# 08-AUDIO_AUX.net
KiCad netlist of a schematic drawn in Altium Designer
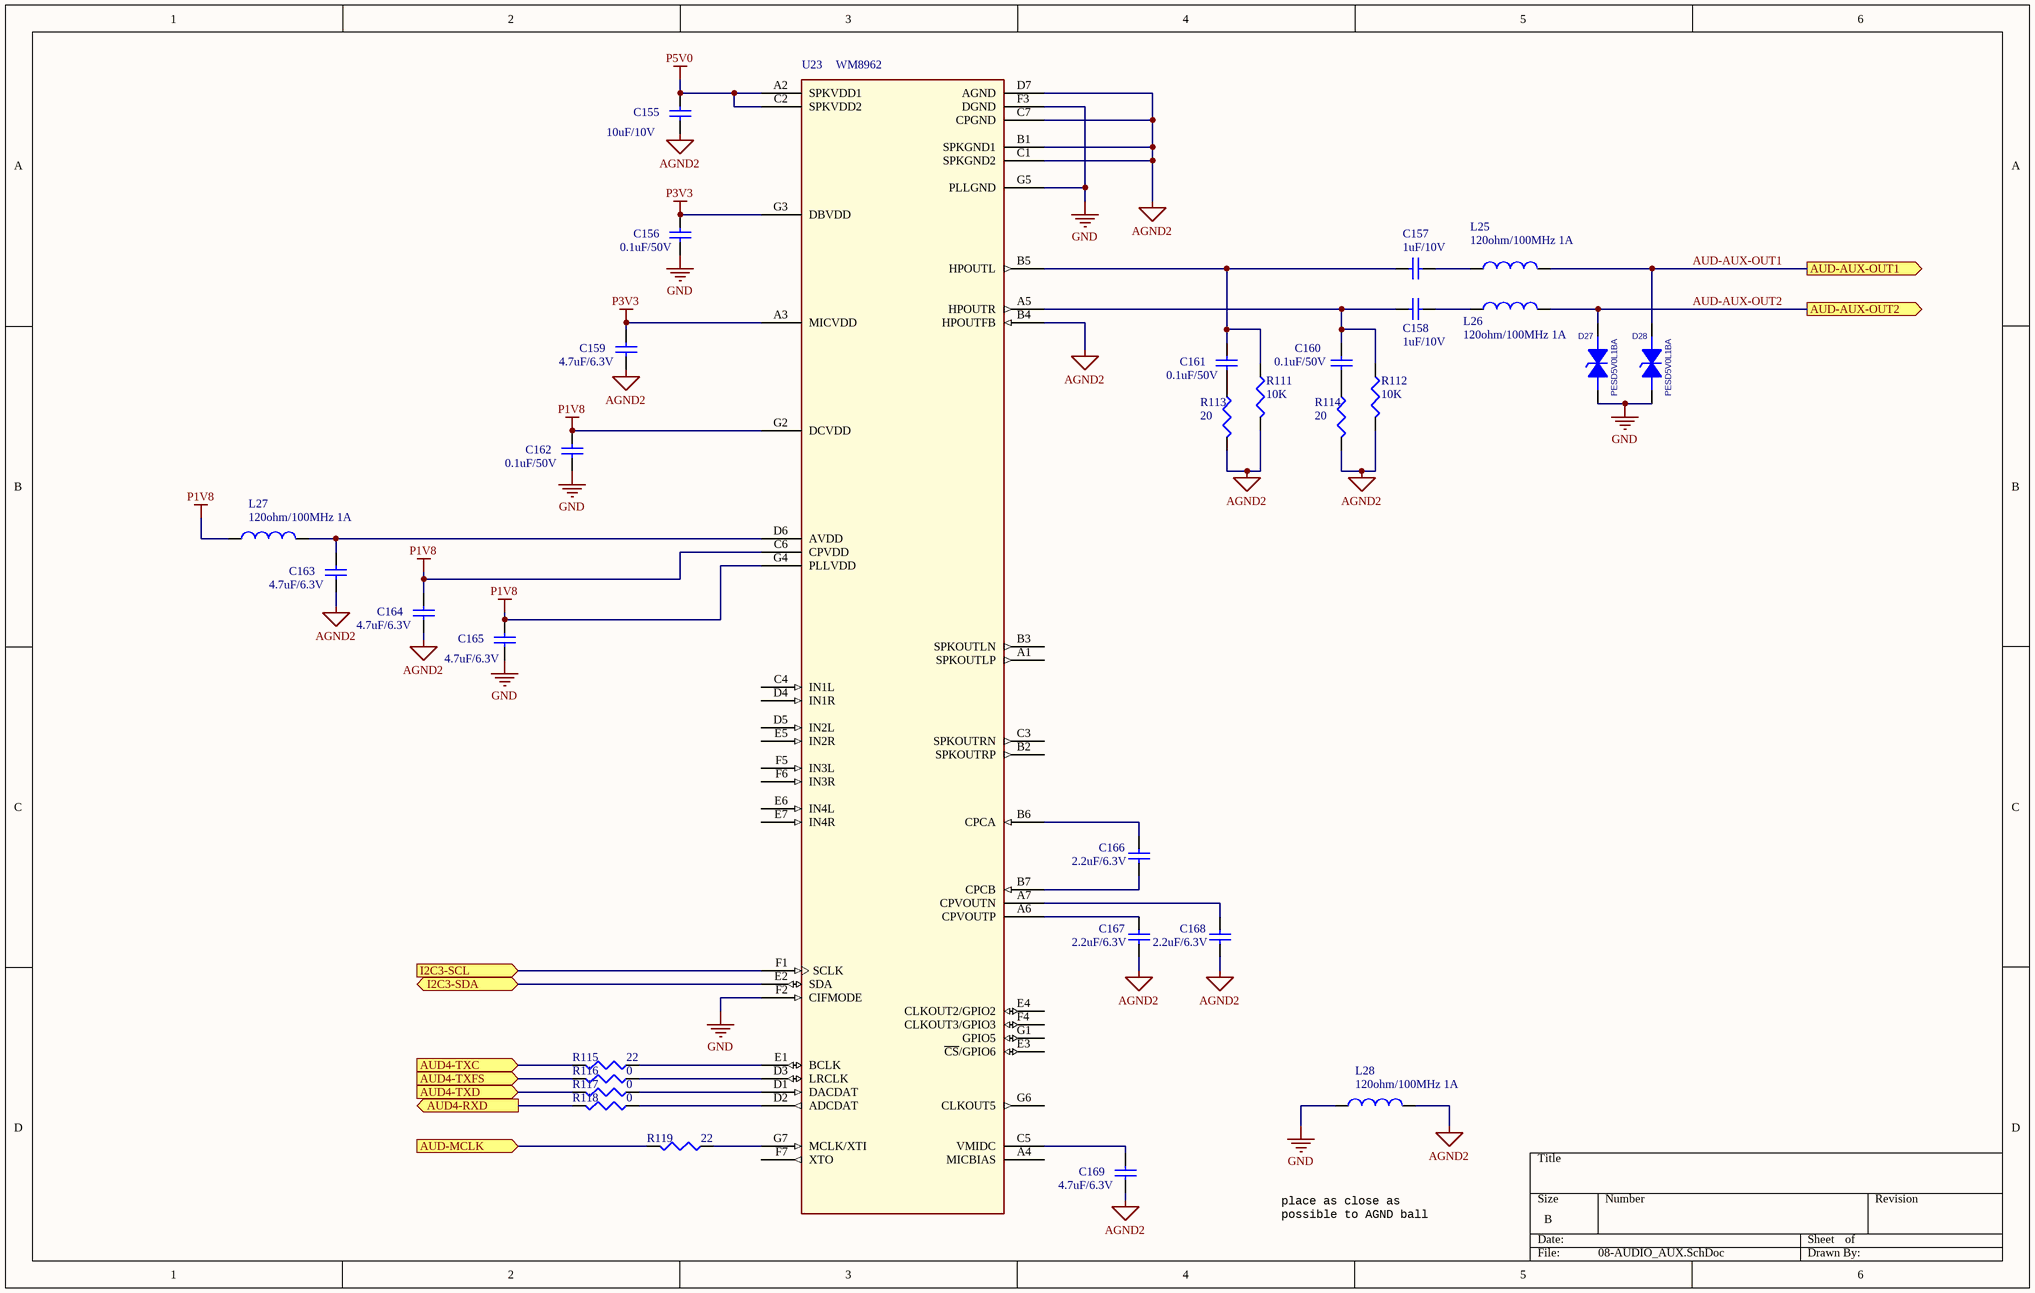
[diagram p0: 08-AUDIO_AUX.SchDoc]

(export (version "E")
  (design (tool "Eeschema 10.0.6"))
  (components
    (comp (ref "C155")
      (value "10uF/10V")
      (footprint "0805")
      (description "Capacitor")
      (fields (field (name "PUBLISHER") "Altium Limited"))
      (libsource (lib "Miscellaneous Devices") (part "Cap"))
    )
    (comp (ref "C156")
      (value "0.1uF/50V")
      (footprint "0402")
      (description "Capacitor")
      (fields (field (name "PUBLISHER") "Altium Limited"))
      (libsource (lib "Miscellaneous Devices") (part "Cap"))
    )
    (comp (ref "C157")
      (value "1uF/10V")
      (footprint "0402")
      (description "Capacitor")
      (fields (field (name "PUBLISHER") "Altium Limited"))
      (libsource (lib "Miscellaneous Devices") (part "Cap"))
    )
    (comp (ref "C158")
      (value "1uF/10V")
      (footprint "0402")
      (description "Capacitor")
      (fields (field (name "PUBLISHER") "Altium Limited"))
      (libsource (lib "Miscellaneous Devices") (part "Cap"))
    )
    (comp (ref "C159")
      (value "4.7uF/6.3V")
      (footprint "0603")
      (description "Capacitor")
      (fields (field (name "PUBLISHER") "Altium Limited"))
      (libsource (lib "Miscellaneous Devices") (part "Cap"))
    )
    (comp (ref "C160")
      (value "0.1uF/50V")
      (footprint "0402")
      (description "Capacitor")
      (fields (field (name "PUBLISHER") "Altium Limited"))
      (libsource (lib "Miscellaneous Devices") (part "Cap"))
    )
    (comp (ref "C161")
      (value "0.1uF/50V")
      (footprint "0402")
      (description "Capacitor")
      (fields (field (name "PUBLISHER") "Altium Limited"))
      (libsource (lib "Miscellaneous Devices") (part "Cap"))
    )
    (comp (ref "C162")
      (value "0.1uF/50V")
      (footprint "0402")
      (description "Capacitor")
      (fields (field (name "PUBLISHER") "Altium Limited"))
      (libsource (lib "Miscellaneous Devices") (part "Cap"))
    )
    (comp (ref "C163")
      (value "4.7uF/6.3V")
      (footprint "0603")
      (description "Capacitor")
      (fields (field (name "PUBLISHER") "Altium Limited"))
      (libsource (lib "Miscellaneous Devices") (part "Cap"))
    )
    (comp (ref "C164")
      (value "4.7uF/6.3V")
      (footprint "0603")
      (description "Capacitor")
      (fields (field (name "PUBLISHER") "Altium Limited"))
      (libsource (lib "Miscellaneous Devices") (part "Cap"))
    )
    (comp (ref "C165")
      (value "4.7uF/6.3V")
      (footprint "0603")
      (description "Capacitor")
      (fields (field (name "PUBLISHER") "Altium Limited"))
      (libsource (lib "Miscellaneous Devices") (part "Cap"))
    )
    (comp (ref "C166")
      (value "2.2uF/6.3V")
      (footprint "0402")
      (description "Capacitor")
      (fields (field (name "PUBLISHER") "Altium Limited"))
      (libsource (lib "Miscellaneous Devices") (part "Cap"))
    )
    (comp (ref "C167")
      (value "2.2uF/6.3V")
      (footprint "0402")
      (description "Capacitor")
      (fields (field (name "PUBLISHER") "Altium Limited"))
      (libsource (lib "Miscellaneous Devices") (part "Cap"))
    )
    (comp (ref "C168")
      (value "2.2uF/6.3V")
      (footprint "0402")
      (description "Capacitor")
      (fields (field (name "PUBLISHER") "Altium Limited"))
      (libsource (lib "Miscellaneous Devices") (part "Cap"))
    )
    (comp (ref "C169")
      (value "4.7uF/6.3V")
      (footprint "0603")
      (description "Capacitor")
      (fields (field (name "PUBLISHER") "Altium Limited"))
      (libsource (lib "Miscellaneous Devices") (part "Cap"))
    )
    (comp (ref "D27") (value "PESD5V0L1BA") (libsource (lib "*") (part "PESD")))
    (comp (ref "D28") (value "PESD5V0L1BA") (libsource (lib "*") (part "PESD")))
    (comp (ref "L25")
      (value "120ohm/100MHz 1A")
      (footprint "0603")
      (description "Inductor")
      (fields (field (name "PUBLISHER") "Altium Limited"))
      (libsource (lib "Miscellaneous Devices") (part "Inductor"))
    )
    (comp (ref "L26")
      (value "120ohm/100MHz 1A")
      (footprint "0603")
      (description "Inductor")
      (fields (field (name "PUBLISHER") "Altium Limited"))
      (libsource (lib "Miscellaneous Devices") (part "Inductor"))
    )
    (comp (ref "L27")
      (value "120ohm/100MHz 1A")
      (footprint "0603")
      (description "Inductor")
      (fields (field (name "PUBLISHER") "Altium Limited"))
      (libsource (lib "Miscellaneous Devices") (part "Inductor"))
    )
    (comp (ref "L28")
      (value "120ohm/100MHz 1A")
      (footprint "0603")
      (description "Inductor")
      (fields (field (name "PUBLISHER") "Altium Limited"))
      (libsource (lib "Miscellaneous Devices") (part "Inductor"))
    )
    (comp (ref "R111") (value "10K") (footprint "0402") (libsource (lib "*") (part "CR16-1003FM")))
    (comp (ref "R112") (value "10K") (footprint "0402") (libsource (lib "*") (part "CR16-1003FM")))
    (comp (ref "R113") (value "20") (footprint "0402") (libsource (lib "*") (part "CR16-1003FM")))
    (comp (ref "R114") (value "20") (footprint "0402") (libsource (lib "*") (part "CR16-1003FM")))
    (comp (ref "R115") (value "22") (footprint "0402") (libsource (lib "*") (part "CR16-1003FM")))
    (comp (ref "R116") (value "0") (footprint "0402") (libsource (lib "*") (part "CR16-1003FM")))
    (comp (ref "R117") (value "0") (footprint "0402") (libsource (lib "*") (part "CR16-1003FM")))
    (comp (ref "R118") (value "0") (footprint "0402") (libsource (lib "*") (part "CR16-1003FM")))
    (comp (ref "R119") (value "22") (footprint "0402") (libsource (lib "*") (part "CR16-1003FM")))
    (comp (ref "U23")
      (value "WM8962")
      (footprint "BGA49")
      (description "IC AUDIO CODEC 24BIT DAC 2 CH ADC 1.8V BGA49")
      (libsource (lib "*") (part "WM8962_BGA_49P_CUST"))
    )
  )
  (nets
    (net (code "1") (name "/AUD-AUX-OUT1") (class "Default")
      (node (ref "D28") (pin "2") (pinfunction "2_2") (pintype "passive"))
      (node (ref "L25") (pin "2") (pinfunction "2_2") (pintype "passive"))
    )
    (net (code "2") (name "/AUD-AUX-OUT2") (class "Default")
      (node (ref "D27") (pin "2") (pinfunction "2_2") (pintype "passive"))
      (node (ref "L26") (pin "2") (pinfunction "2_2") (pintype "passive"))
    )
    (net (code "3") (name "/AUD-MCLK") (class "Default")
      (node (ref "R119") (pin "2") (pinfunction "2_2") (pintype "passive"))
    )
    (net (code "4") (name "/AUD4-RXD") (class "Default")
      (node (ref "R118") (pin "2") (pinfunction "2_2") (pintype "passive"))
    )
    (net (code "5") (name "/AUD4-TXC") (class "Default")
      (node (ref "R115") (pin "2") (pinfunction "2_2") (pintype "passive"))
    )
    (net (code "6") (name "/AUD4-TXD") (class "Default")
      (node (ref "R117") (pin "2") (pinfunction "2_2") (pintype "passive"))
    )
    (net (code "7") (name "/AUD4-TXFS") (class "Default")
      (node (ref "R116") (pin "2") (pinfunction "2_2") (pintype "passive"))
    )
    (net (code "8") (name "/I2C3-SCL") (class "Default")
      (node (ref "U23") (pin "F1") (pinfunction "SCLK_F1") (pintype "input"))
    )
    (net (code "9") (name "/I2C3-SDA") (class "Default")
      (node (ref "U23") (pin "E2") (pinfunction "SDA_E2") (pintype "bidirectional"))
    )
    (net (code "10") (name "AGND2") (class "Default")
      (node (ref "C155") (pin "1") (pinfunction "1_1") (pintype "passive"))
      (node (ref "C159") (pin "1") (pinfunction "1_1") (pintype "passive"))
      (node (ref "C163") (pin "1") (pinfunction "1_1") (pintype "passive"))
      (node (ref "C164") (pin "1") (pinfunction "1_1") (pintype "passive"))
      (node (ref "C167") (pin "1") (pinfunction "1_1") (pintype "passive"))
      (node (ref "C168") (pin "1") (pinfunction "1_1") (pintype "passive"))
      (node (ref "C169") (pin "1") (pinfunction "1_1") (pintype "passive"))
      (node (ref "L28") (pin "2") (pinfunction "2_2") (pintype "passive"))
      (node (ref "R111") (pin "2") (pinfunction "2_2") (pintype "passive"))
      (node (ref "R112") (pin "2") (pinfunction "2_2") (pintype "passive"))
      (node (ref "R113") (pin "2") (pinfunction "2_2") (pintype "passive"))
      (node (ref "R114") (pin "2") (pinfunction "2_2") (pintype "passive"))
      (node (ref "U23") (pin "B1") (pinfunction "SPKGND1_B1") (pintype "power_in"))
      (node (ref "U23") (pin "B4") (pinfunction "HPOUTFB_B4") (pintype "input"))
      (node (ref "U23") (pin "C1") (pinfunction "SPKGND2_C1") (pintype "power_in"))
      (node (ref "U23") (pin "C7") (pinfunction "CPGND_C7") (pintype "power_in"))
      (node (ref "U23") (pin "D7") (pinfunction "AGND_D7") (pintype "power_in"))
    )
    (net (code "11") (name "GND") (class "Default")
      (node (ref "C156") (pin "1") (pinfunction "1_1") (pintype "passive"))
      (node (ref "C162") (pin "1") (pinfunction "1_1") (pintype "passive"))
      (node (ref "C165") (pin "1") (pinfunction "1_1") (pintype "passive"))
      (node (ref "D27") (pin "1") (pinfunction "1_1") (pintype "passive"))
      (node (ref "D28") (pin "1") (pinfunction "1_1") (pintype "passive"))
      (node (ref "L28") (pin "1") (pinfunction "1_1") (pintype "passive"))
      (node (ref "U23") (pin "F2") (pinfunction "CIFMODE_F2") (pintype "input"))
      (node (ref "U23") (pin "F3") (pinfunction "DGND_F3") (pintype "power_in"))
      (node (ref "U23") (pin "G5") (pinfunction "PLLGND_G5") (pintype "power_in"))
    )
    (net (code "12") (name "Net-(C157-Pad1)") (class "Default")
      (node (ref "C157") (pin "1") (pinfunction "1_1") (pintype "passive"))
      (node (ref "L25") (pin "1") (pinfunction "1_1") (pintype "passive"))
    )
    (net (code "13") (name "Net-(C158-Pad1)") (class "Default")
      (node (ref "C158") (pin "1") (pinfunction "1_1") (pintype "passive"))
      (node (ref "L26") (pin "1") (pinfunction "1_1") (pintype "passive"))
    )
    (net (code "14") (name "Net-(C160-Pad1)") (class "Default")
      (node (ref "C160") (pin "1") (pinfunction "1_1") (pintype "passive"))
      (node (ref "R114") (pin "1") (pinfunction "1_1") (pintype "passive"))
    )
    (net (code "15") (name "Net-(C161-Pad1)") (class "Default")
      (node (ref "C161") (pin "1") (pinfunction "1_1") (pintype "passive"))
      (node (ref "R113") (pin "1") (pinfunction "1_1") (pintype "passive"))
    )
    (net (code "16") (name "Net-(U23-ADCDAT)") (class "Default")
      (node (ref "R118") (pin "1") (pinfunction "1_1") (pintype "passive"))
      (node (ref "U23") (pin "D2") (pinfunction "ADCDAT_D2") (pintype "output"))
    )
    (net (code "17") (name "Net-(U23-AVDD)") (class "Default")
      (node (ref "C163") (pin "2") (pinfunction "2_2") (pintype "passive"))
      (node (ref "L27") (pin "2") (pinfunction "2_2") (pintype "passive"))
      (node (ref "U23") (pin "D6") (pinfunction "AVDD_D6") (pintype "power_in"))
    )
    (net (code "18") (name "Net-(U23-BCLK)") (class "Default")
      (node (ref "R115") (pin "1") (pinfunction "1_1") (pintype "passive"))
      (node (ref "U23") (pin "E1") (pinfunction "BCLK_E1") (pintype "bidirectional"))
    )
    (net (code "19") (name "Net-(U23-CPCA)") (class "Default")
      (node (ref "C166") (pin "2") (pinfunction "2_2") (pintype "passive"))
      (node (ref "U23") (pin "B6") (pinfunction "CPCA_B6") (pintype "input"))
    )
    (net (code "20") (name "Net-(U23-CPCB)") (class "Default")
      (node (ref "C166") (pin "1") (pinfunction "1_1") (pintype "passive"))
      (node (ref "U23") (pin "B7") (pinfunction "CPCB_B7") (pintype "input"))
    )
    (net (code "21") (name "Net-(U23-CPVOUTN)") (class "Default")
      (node (ref "C168") (pin "2") (pinfunction "2_2") (pintype "passive"))
      (node (ref "U23") (pin "A7") (pinfunction "CPVOUTN_A7") (pintype "power_in"))
    )
    (net (code "22") (name "Net-(U23-CPVOUTP)") (class "Default")
      (node (ref "C167") (pin "2") (pinfunction "2_2") (pintype "passive"))
      (node (ref "U23") (pin "A6") (pinfunction "CPVOUTP_A6") (pintype "power_in"))
    )
    (net (code "23") (name "Net-(U23-DACDAT)") (class "Default")
      (node (ref "R117") (pin "1") (pinfunction "1_1") (pintype "passive"))
      (node (ref "U23") (pin "D1") (pinfunction "DACDAT_D1") (pintype "input"))
    )
    (net (code "24") (name "Net-(U23-HPOUTL)") (class "Default")
      (node (ref "C157") (pin "2") (pinfunction "2_2") (pintype "passive"))
      (node (ref "C161") (pin "2") (pinfunction "2_2") (pintype "passive"))
      (node (ref "R111") (pin "1") (pinfunction "1_1") (pintype "passive"))
      (node (ref "U23") (pin "B5") (pinfunction "HPOUTL_B5") (pintype "output"))
    )
    (net (code "25") (name "Net-(U23-HPOUTR)") (class "Default")
      (node (ref "C158") (pin "2") (pinfunction "2_2") (pintype "passive"))
      (node (ref "C160") (pin "2") (pinfunction "2_2") (pintype "passive"))
      (node (ref "R112") (pin "1") (pinfunction "1_1") (pintype "passive"))
      (node (ref "U23") (pin "A5") (pinfunction "HPOUTR_A5") (pintype "output"))
    )
    (net (code "26") (name "Net-(U23-LRCLK)") (class "Default")
      (node (ref "R116") (pin "1") (pinfunction "1_1") (pintype "passive"))
      (node (ref "U23") (pin "D3") (pinfunction "LRCLK_D3") (pintype "bidirectional"))
    )
    (net (code "27") (name "Net-(U23-MCLK{slash}XTI)") (class "Default")
      (node (ref "R119") (pin "1") (pinfunction "1_1") (pintype "passive"))
      (node (ref "U23") (pin "G7") (pinfunction "MCLK/XTI_G7") (pintype "input"))
    )
    (net (code "28") (name "Net-(U23-VMIDC)") (class "Default")
      (node (ref "C169") (pin "2") (pinfunction "2_2") (pintype "passive"))
      (node (ref "U23") (pin "C5") (pinfunction "VMIDC_C5") (pintype "power_in"))
    )
    (net (code "29") (name "P1V8") (class "Default")
      (node (ref "C162") (pin "2") (pinfunction "2_2") (pintype "passive"))
      (node (ref "C164") (pin "2") (pinfunction "2_2") (pintype "passive"))
      (node (ref "C165") (pin "2") (pinfunction "2_2") (pintype "passive"))
      (node (ref "L27") (pin "1") (pinfunction "1_1") (pintype "passive"))
      (node (ref "U23") (pin "C6") (pinfunction "CPVDD_C6") (pintype "power_in"))
      (node (ref "U23") (pin "G2") (pinfunction "DCVDD_G2") (pintype "power_in"))
      (node (ref "U23") (pin "G4") (pinfunction "PLLVDD_G4") (pintype "power_in"))
    )
    (net (code "30") (name "P3V3") (class "Default")
      (node (ref "C156") (pin "2") (pinfunction "2_2") (pintype "passive"))
      (node (ref "C159") (pin "2") (pinfunction "2_2") (pintype "passive"))
      (node (ref "U23") (pin "A3") (pinfunction "MICVDD_A3") (pintype "power_in"))
      (node (ref "U23") (pin "G3") (pinfunction "DBVDD_G3") (pintype "power_in"))
    )
    (net (code "31") (name "P5V0") (class "Default")
      (node (ref "C155") (pin "2") (pinfunction "2_2") (pintype "passive"))
      (node (ref "U23") (pin "A2") (pinfunction "SPKVDD1_A2") (pintype "power_in"))
      (node (ref "U23") (pin "C2") (pinfunction "SPKVDD2_C2") (pintype "power_in"))
    )
    (net (code "32") (name "unconnected-(U23-CLKOUT2{slash}GPIO2-PadE4)") (class "Default")
      (node (ref "U23") (pin "E4") (pinfunction "CLKOUT2/GPIO2_E4") (pintype "bidirectional"))
    )
    (net (code "33") (name "unconnected-(U23-CLKOUT3{slash}GPIO3-PadF4)") (class "Default")
      (node (ref "U23") (pin "F4") (pinfunction "CLKOUT3/GPIO3_F4") (pintype "bidirectional"))
    )
    (net (code "34") (name "unconnected-(U23-CLKOUT5-PadG6)") (class "Default")
      (node (ref "U23") (pin "G6") (pinfunction "CLKOUT5_G6") (pintype "output"))
    )
    (net (code "35") (name "unconnected-(U23-GPIO5-PadG1)") (class "Default")
      (node (ref "U23") (pin "G1") (pinfunction "GPIO5_G1") (pintype "bidirectional"))
    )
    (net (code "36") (name "unconnected-(U23-IN1L-PadC4)") (class "Default")
      (node (ref "U23") (pin "C4") (pinfunction "IN1L_C4") (pintype "input"))
    )
    (net (code "37") (name "unconnected-(U23-IN1R-PadD4)") (class "Default")
      (node (ref "U23") (pin "D4") (pinfunction "IN1R_D4") (pintype "input"))
    )
    (net (code "38") (name "unconnected-(U23-IN2L-PadD5)") (class "Default")
      (node (ref "U23") (pin "D5") (pinfunction "IN2L_D5") (pintype "input"))
    )
    (net (code "39") (name "unconnected-(U23-IN2R-PadE5)") (class "Default")
      (node (ref "U23") (pin "E5") (pinfunction "IN2R_E5") (pintype "input"))
    )
    (net (code "40") (name "unconnected-(U23-IN3L-PadF5)") (class "Default")
      (node (ref "U23") (pin "F5") (pinfunction "IN3L_F5") (pintype "input"))
    )
    (net (code "41") (name "unconnected-(U23-IN3R-PadF6)") (class "Default")
      (node (ref "U23") (pin "F6") (pinfunction "IN3R_F6") (pintype "input"))
    )
    (net (code "42") (name "unconnected-(U23-IN4L-PadE6)") (class "Default")
      (node (ref "U23") (pin "E6") (pinfunction "IN4L_E6") (pintype "input"))
    )
    (net (code "43") (name "unconnected-(U23-IN4R-PadE7)") (class "Default")
      (node (ref "U23") (pin "E7") (pinfunction "IN4R_E7") (pintype "input"))
    )
    (net (code "44") (name "unconnected-(U23-MICBIAS-PadA4)") (class "Default")
      (node (ref "U23") (pin "A4") (pinfunction "MICBIAS_A4") (pintype "passive"))
    )
    (net (code "45") (name "unconnected-(U23-SPKOUTLN-PadB3)") (class "Default")
      (node (ref "U23") (pin "B3") (pinfunction "SPKOUTLN_B3") (pintype "output"))
    )
    (net (code "46") (name "unconnected-(U23-SPKOUTLP-PadA1)") (class "Default")
      (node (ref "U23") (pin "A1") (pinfunction "SPKOUTLP_A1") (pintype "output"))
    )
    (net (code "47") (name "unconnected-(U23-SPKOUTRN-PadC3)") (class "Default")
      (node (ref "U23") (pin "C3") (pinfunction "SPKOUTRN_C3") (pintype "output"))
    )
    (net (code "48") (name "unconnected-(U23-SPKOUTRP-PadB2)") (class "Default")
      (node (ref "U23") (pin "B2") (pinfunction "SPKOUTRP_B2") (pintype "output"))
    )
    (net (code "49") (name "unconnected-(U23-XTO-PadF7)") (class "Default")
      (node (ref "U23") (pin "F7") (pinfunction "XTO_F7") (pintype "output"))
    )
    (net (code "50") (name "unconnected-(U23-~{CS}{slash}GPIO6-PadE3)") (class "Default")
      (node (ref "U23") (pin "E3") (pinfunction "~{CS}/GPIO6_E3") (pintype "bidirectional"))
    )
  )
)
